# happytuesdays.net
KiCad netlist of a schematic drawn in EAGLE
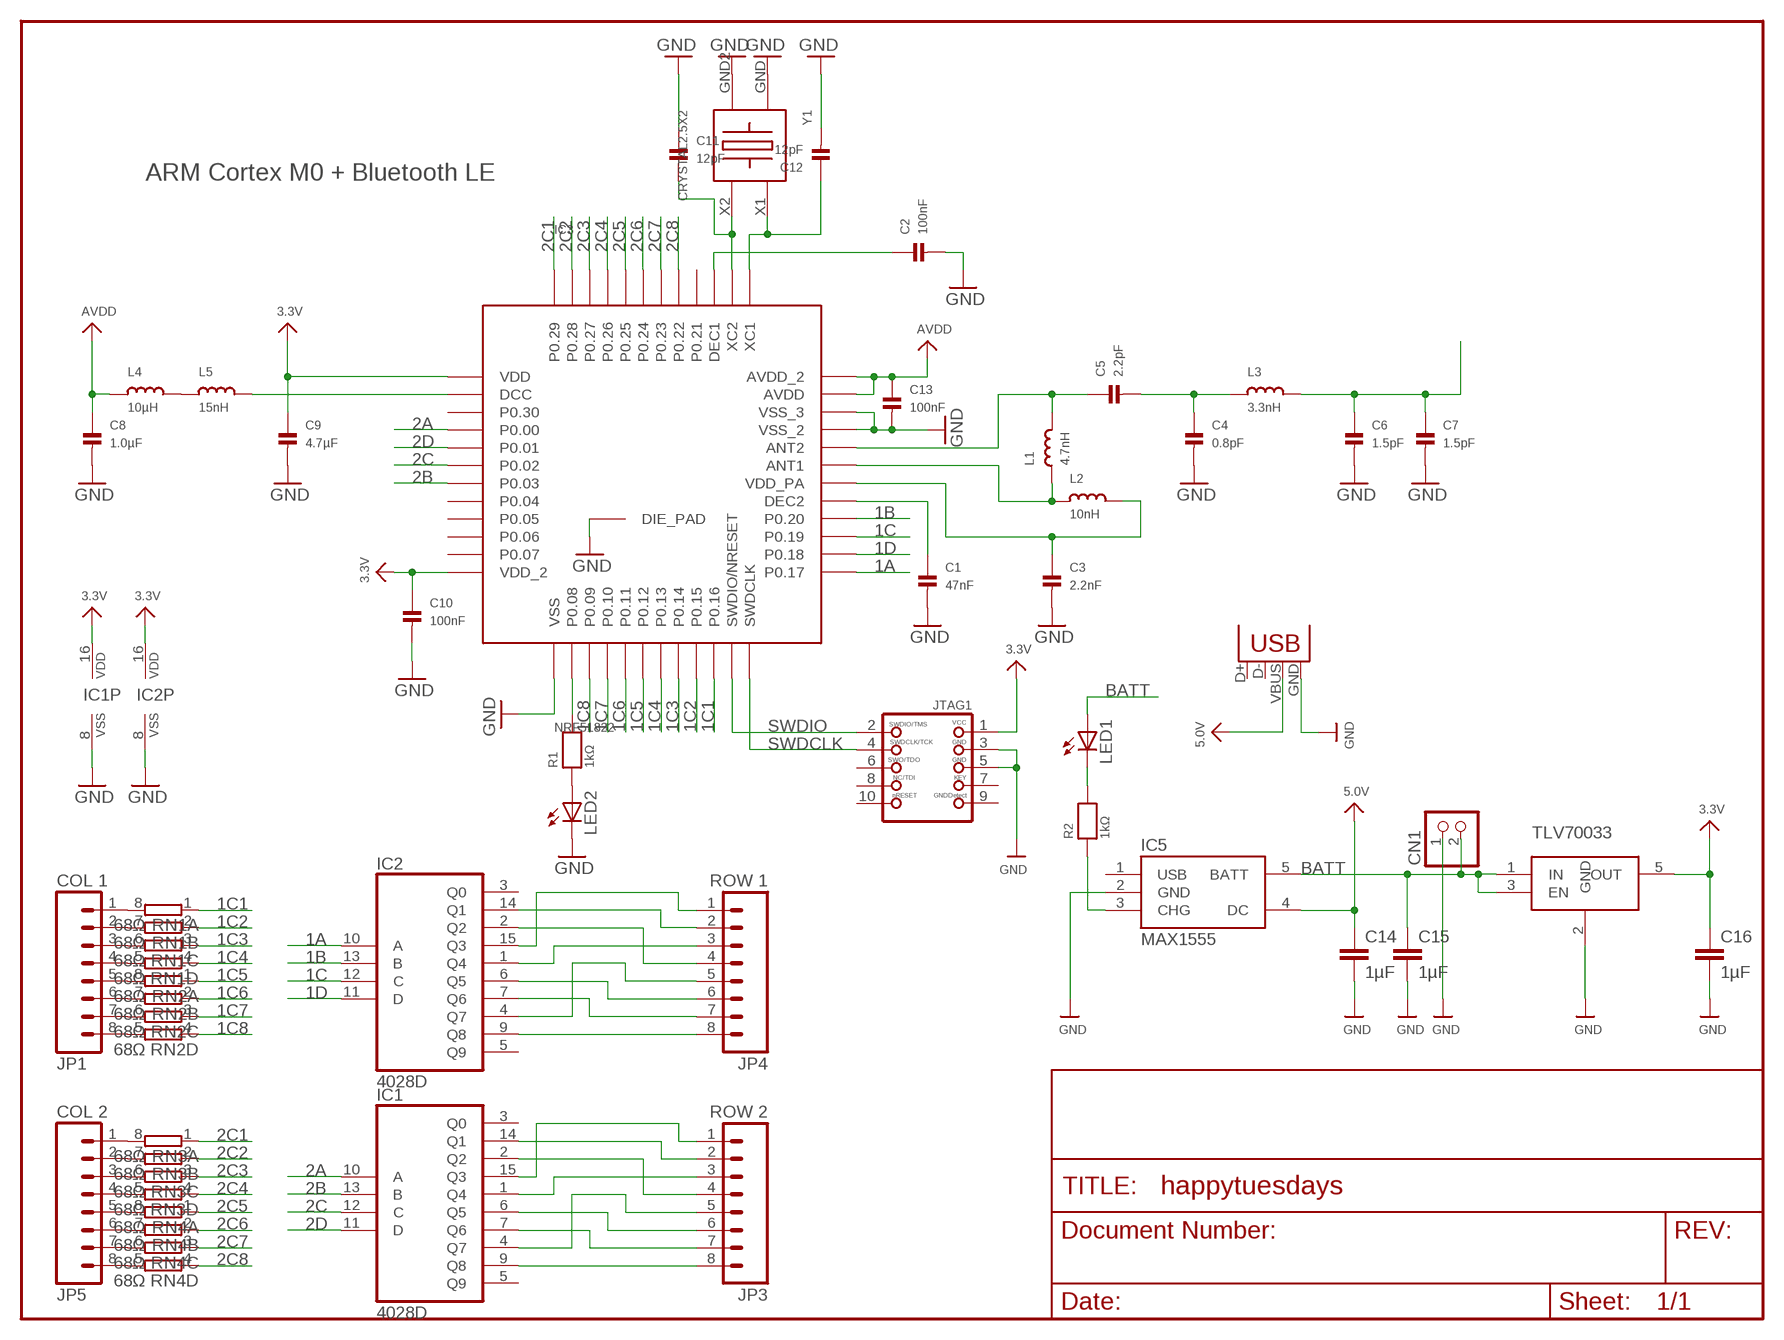
[diagram p0: schematic, sheet 1]

(export (version "E")
  (design (tool "Eeschema 10.0.6"))
  (components
    (comp (ref "C1")
      (value "47nF")
      (footprint "eagle-import:_0402")
      (libsource (lib "eagle-import") (part "CAP_CERAMIC_0402"))
    )
    (comp (ref "C2")
      (value "100nF")
      (footprint "eagle-import:_0402")
      (libsource (lib "eagle-import") (part "CAP_CERAMIC_0402"))
    )
    (comp (ref "C3")
      (value "2.2nF")
      (footprint "eagle-import:_0402")
      (libsource (lib "eagle-import") (part "CAP_CERAMIC_0402"))
    )
    (comp (ref "C4")
      (value "0.8pF")
      (footprint "eagle-import:_0402")
      (libsource (lib "eagle-import") (part "CAP_CERAMIC_0402"))
    )
    (comp (ref "C5")
      (value "2.2pF")
      (footprint "eagle-import:_0402")
      (libsource (lib "eagle-import") (part "CAP_CERAMIC_0402"))
    )
    (comp (ref "C6")
      (value "1.5pF")
      (footprint "eagle-import:_0402")
      (libsource (lib "eagle-import") (part "CAP_CERAMIC_0402"))
    )
    (comp (ref "C7")
      (value "1.5pF")
      (footprint "eagle-import:_0402")
      (libsource (lib "eagle-import") (part "CAP_CERAMIC_0402"))
    )
    (comp (ref "C8")
      (value "1.0µF")
      (footprint "eagle-import:_0402")
      (libsource (lib "eagle-import") (part "CAP_CERAMIC_0402"))
    )
    (comp (ref "C9")
      (value "4.7µF")
      (footprint "eagle-import:_0402")
      (libsource (lib "eagle-import") (part "CAP_CERAMIC_0402"))
    )
    (comp (ref "C10")
      (value "100nF")
      (footprint "eagle-import:_0402")
      (libsource (lib "eagle-import") (part "CAP_CERAMIC_0402"))
    )
    (comp (ref "C11")
      (value "12pF")
      (footprint "eagle-import:_0402")
      (libsource (lib "eagle-import") (part "CAP_CERAMIC_0402"))
    )
    (comp (ref "C12")
      (value "12pF")
      (footprint "eagle-import:_0402")
      (libsource (lib "eagle-import") (part "CAP_CERAMIC_0402"))
    )
    (comp (ref "C13")
      (value "100nF")
      (footprint "eagle-import:_0402")
      (libsource (lib "eagle-import") (part "CAP_CERAMIC_0402"))
    )
    (comp (ref "C14")
      (value "1µF")
      (footprint "eagle-import:C0603K")
      (libsource (lib "eagle-import") (part "C-EUC0603K"))
    )
    (comp (ref "C15")
      (value "1µF")
      (footprint "eagle-import:C0603K")
      (libsource (lib "eagle-import") (part "C-EUC0603K"))
    )
    (comp (ref "C16")
      (value "1µF")
      (footprint "eagle-import:C0603K")
      (libsource (lib "eagle-import") (part "C-EUC0603K"))
    )
    (comp (ref "CN1")
      (value "JST_2PIN")
      (footprint "eagle-import:JSTPH2")
      (libsource (lib "eagle-import") (part "JST_2PIN"))
    )
    (comp (ref "IC1")
      (value "4028D")
      (footprint "eagle-import:SO16")
      (libsource (lib "eagle-import") (part "4028D"))
    )
    (comp (ref "IC2")
      (value "4028D")
      (footprint "eagle-import:SO16")
      (libsource (lib "eagle-import") (part "4028D"))
    )
    (comp (ref "IC3")
      (value "NRF51822")
      (footprint "eagle-import:QFN48")
      (libsource (lib "eagle-import") (part "NRF51822"))
    )
    (comp (ref "IC4")
      (value "TLV70033DCK")
      (footprint "eagle-import:SC70-5L")
      (libsource (lib "eagle-import") (part "TLV700DCK"))
    )
    (comp (ref "IC5")
      (value "MAX1555")
      (footprint "eagle-import:SOT23-5")
      (libsource (lib "eagle-import") (part "MAX1555"))
    )
    (comp (ref "JP1")
      (value "COL 1")
      (footprint "eagle-import:1X08_LOCK")
      (libsource (lib "eagle-import") (part "M08LOCK"))
    )
    (comp (ref "JP3")
      (value "ROW 2")
      (footprint "eagle-import:1X08_LOCK")
      (libsource (lib "eagle-import") (part "M08LOCK"))
    )
    (comp (ref "JP4")
      (value "ROW 1")
      (footprint "eagle-import:1X08_LOCK")
      (libsource (lib "eagle-import") (part "M08LOCK"))
    )
    (comp (ref "JP5")
      (value "COL 2")
      (footprint "eagle-import:1X08_LOCK")
      (libsource (lib "eagle-import") (part "M08LOCK"))
    )
    (comp (ref "JTAG1")
      (value "JTAG-CORTEXM3SMT")
      (footprint "eagle-import:2X05_1.27MM_SMT")
      (libsource (lib "eagle-import") (part "JTAG-CORTEXM3SMT"))
    )
    (comp (ref "L1")
      (value "4.7nH")
      (footprint "eagle-import:_0402")
      (libsource (lib "eagle-import") (part "INDUCTOR_0402"))
    )
    (comp (ref "L2")
      (value "10nH")
      (footprint "eagle-import:_0402")
      (libsource (lib "eagle-import") (part "INDUCTOR_0402"))
    )
    (comp (ref "L3")
      (value "3.3nH")
      (footprint "eagle-import:_0402")
      (libsource (lib "eagle-import") (part "INDUCTOR_0402"))
    )
    (comp (ref "L4")
      (value "10µH")
      (footprint "eagle-import:_0402")
      (libsource (lib "eagle-import") (part "INDUCTOR_0402"))
    )
    (comp (ref "L5")
      (value "15nH")
      (footprint "eagle-import:_0402")
      (libsource (lib "eagle-import") (part "INDUCTOR_0402"))
    )
    (comp (ref "LED1")
      (value "LEDCHIPLED_0603")
      (footprint "eagle-import:CHIPLED_0603")
      (libsource (lib "eagle-import") (part "LEDCHIPLED_0603"))
    )
    (comp (ref "LED2")
      (value "LEDCHIPLED_0603")
      (footprint "eagle-import:CHIPLED_0603")
      (libsource (lib "eagle-import") (part "LEDCHIPLED_0603"))
    )
    (comp (ref "R1")
      (value "1kΩ")
      (footprint "eagle-import:_0402")
      (libsource (lib "eagle-import") (part "RESISTOR_0402"))
    )
    (comp (ref "R2")
      (value "1kΩ")
      (footprint "eagle-import:_0402")
      (libsource (lib "eagle-import") (part "RESISTOR_0402"))
    )
    (comp (ref "RN1")
      (value "68Ω")
      (footprint "eagle-import:4X0402ARV341")
      (libsource (lib "eagle-import") (part "4R-N0402ARV341"))
    )
    (comp (ref "RN2")
      (value "68Ω")
      (footprint "eagle-import:4X0402ARV341")
      (libsource (lib "eagle-import") (part "4R-N0402ARV341"))
    )
    (comp (ref "RN3")
      (value "68Ω")
      (footprint "eagle-import:4X0402ARV341")
      (libsource (lib "eagle-import") (part "4R-N0402ARV341"))
    )
    (comp (ref "RN4")
      (value "68Ω")
      (footprint "eagle-import:4X0402ARV341")
      (libsource (lib "eagle-import") (part "4R-N0402ARV341"))
    )
    (comp (ref "X1")
      (value "USB-MICROB")
      (footprint "eagle-import:USB-MICROB")
      (libsource (lib "eagle-import") (part "USB-MICROB"))
    )
    (comp (ref "Y1")
      (value "CRYSTAL2.5X2")
      (footprint "eagle-import:2.5X2MM")
      (libsource (lib "eagle-import") (part "CRYSTAL2.5X2"))
    )
  )
  (nets
    (net (code "1") (name "/1A") (class "Default")
      (node (ref "IC2") (pin "10") (pinfunction "A_10") (pintype "input"))
      (node (ref "IC3") (pin "25") (pinfunction "P0.17_25") (pintype "bidirectional"))
    )
    (net (code "2") (name "/1B") (class "Default")
      (node (ref "IC2") (pin "13") (pinfunction "B_13") (pintype "input"))
      (node (ref "IC3") (pin "28") (pinfunction "P0.20_28") (pintype "bidirectional"))
    )
    (net (code "3") (name "/1C") (class "Default")
      (node (ref "IC2") (pin "12") (pinfunction "C_12") (pintype "input"))
      (node (ref "IC3") (pin "27") (pinfunction "P0.19_27") (pintype "bidirectional"))
    )
    (net (code "4") (name "/1C1") (class "Default")
      (node (ref "IC3") (pin "22") (pinfunction "P0.16_22") (pintype "bidirectional"))
      (node (ref "RN1") (pin "1") (pinfunction "1_1") (pintype "passive"))
    )
    (net (code "5") (name "/1C2") (class "Default")
      (node (ref "IC3") (pin "21") (pinfunction "P0.15_21") (pintype "bidirectional"))
      (node (ref "RN1") (pin "2") (pinfunction "1_2") (pintype "passive"))
    )
    (net (code "6") (name "/1C3") (class "Default")
      (node (ref "IC3") (pin "20") (pinfunction "P0.14_20") (pintype "bidirectional"))
      (node (ref "RN1") (pin "3") (pinfunction "1_3") (pintype "passive"))
    )
    (net (code "7") (name "/1C4") (class "Default")
      (node (ref "IC3") (pin "19") (pinfunction "P0.13_19") (pintype "bidirectional"))
      (node (ref "RN1") (pin "4") (pinfunction "1_4") (pintype "passive"))
    )
    (net (code "8") (name "/1C5") (class "Default")
      (node (ref "IC3") (pin "18") (pinfunction "P0.12_18") (pintype "bidirectional"))
      (node (ref "RN2") (pin "1") (pinfunction "1_1") (pintype "passive"))
    )
    (net (code "9") (name "/1C6") (class "Default")
      (node (ref "IC3") (pin "17") (pinfunction "P0.11_17") (pintype "bidirectional"))
      (node (ref "RN2") (pin "2") (pinfunction "1_2") (pintype "passive"))
    )
    (net (code "10") (name "/1C7") (class "Default")
      (node (ref "IC3") (pin "16") (pinfunction "P0.10_16") (pintype "bidirectional"))
      (node (ref "RN2") (pin "3") (pinfunction "1_3") (pintype "passive"))
    )
    (net (code "11") (name "/1C8") (class "Default")
      (node (ref "IC3") (pin "15") (pinfunction "P0.09_15") (pintype "bidirectional"))
      (node (ref "RN2") (pin "4") (pinfunction "1_4") (pintype "passive"))
    )
    (net (code "12") (name "/1D") (class "Default")
      (node (ref "IC2") (pin "11") (pinfunction "D_11") (pintype "input"))
      (node (ref "IC3") (pin "26") (pinfunction "P0.18_26") (pintype "bidirectional"))
    )
    (net (code "13") (name "/2A") (class "Default")
      (node (ref "IC1") (pin "10") (pinfunction "A_10") (pintype "input"))
      (node (ref "IC3") (pin "4") (pinfunction "P0.00_4") (pintype "bidirectional"))
    )
    (net (code "14") (name "/2B") (class "Default")
      (node (ref "IC1") (pin "13") (pinfunction "B_13") (pintype "input"))
      (node (ref "IC3") (pin "7") (pinfunction "P0.03_7") (pintype "bidirectional"))
    )
    (net (code "15") (name "/2C") (class "Default")
      (node (ref "IC1") (pin "12") (pinfunction "C_12") (pintype "input"))
      (node (ref "IC3") (pin "6") (pinfunction "P0.02_6") (pintype "bidirectional"))
    )
    (net (code "16") (name "/2C1") (class "Default")
      (node (ref "IC3") (pin "48") (pinfunction "P0.29_48") (pintype "bidirectional"))
      (node (ref "RN3") (pin "1") (pinfunction "1_1") (pintype "passive"))
    )
    (net (code "17") (name "/2C2") (class "Default")
      (node (ref "IC3") (pin "47") (pinfunction "P0.28_47") (pintype "bidirectional"))
      (node (ref "RN3") (pin "2") (pinfunction "1_2") (pintype "passive"))
    )
    (net (code "18") (name "/2C3") (class "Default")
      (node (ref "IC3") (pin "46") (pinfunction "P0.27_46") (pintype "bidirectional"))
      (node (ref "RN3") (pin "3") (pinfunction "1_3") (pintype "passive"))
    )
    (net (code "19") (name "/2C4") (class "Default")
      (node (ref "IC3") (pin "45") (pinfunction "P0.26_45") (pintype "bidirectional"))
      (node (ref "RN3") (pin "4") (pinfunction "1_4") (pintype "passive"))
    )
    (net (code "20") (name "/2C5") (class "Default")
      (node (ref "IC3") (pin "44") (pinfunction "P0.25_44") (pintype "bidirectional"))
      (node (ref "RN4") (pin "1") (pinfunction "1_1") (pintype "passive"))
    )
    (net (code "21") (name "/2C6") (class "Default")
      (node (ref "IC3") (pin "43") (pinfunction "P0.24_43") (pintype "bidirectional"))
      (node (ref "RN4") (pin "2") (pinfunction "1_2") (pintype "passive"))
    )
    (net (code "22") (name "/2C7") (class "Default")
      (node (ref "IC3") (pin "42") (pinfunction "P0.23_42") (pintype "bidirectional"))
      (node (ref "RN4") (pin "3") (pinfunction "1_3") (pintype "passive"))
    )
    (net (code "23") (name "/2C8") (class "Default")
      (node (ref "IC3") (pin "41") (pinfunction "P0.22_41") (pintype "bidirectional"))
      (node (ref "RN4") (pin "4") (pinfunction "1_4") (pintype "passive"))
    )
    (net (code "24") (name "/2D") (class "Default")
      (node (ref "IC1") (pin "11") (pinfunction "D_11") (pintype "input"))
      (node (ref "IC3") (pin "5") (pinfunction "P0.01_5") (pintype "bidirectional"))
    )
    (net (code "25") (name "/BATT") (class "Default")
      (node (ref "C15") (pin "1") (pinfunction "1_1") (pintype "passive"))
      (node (ref "CN1") (pin "2") (pinfunction "2_2") (pintype "passive"))
      (node (ref "IC4") (pin "1") (pinfunction "IN_1") (pintype "bidirectional"))
      (node (ref "IC4") (pin "3") (pinfunction "EN_3") (pintype "bidirectional"))
      (node (ref "IC5") (pin "5") (pinfunction "BATT_5") (pintype "bidirectional"))
      (node (ref "LED1") (pin "A") (pinfunction "A_A") (pintype "passive"))
    )
    (net (code "26") (name "/SWDCLK") (class "Default")
      (node (ref "IC3") (pin "24") (pinfunction "SWDCLK_24") (pintype "bidirectional"))
      (node (ref "JTAG1") (pin "4") (pinfunction "4_4") (pintype "passive"))
    )
    (net (code "27") (name "/SWDIO") (class "Default")
      (node (ref "IC3") (pin "23") (pinfunction "SWDIO/NRESET_23") (pintype "bidirectional"))
      (node (ref "JTAG1") (pin "2") (pinfunction "2_2") (pintype "passive"))
    )
    (net (code "28") (name "3.3V") (class "Default")
      (node (ref "C10") (pin "1") (pinfunction "P$1_1") (pintype "passive"))
      (node (ref "C16") (pin "1") (pinfunction "1_1") (pintype "passive"))
      (node (ref "C9") (pin "1") (pinfunction "P$1_1") (pintype "passive"))
      (node (ref "IC1") (pin "16") (pinfunction "VDD_16") (pintype "power_in"))
      (node (ref "IC2") (pin "16") (pinfunction "VDD_16") (pintype "power_in"))
      (node (ref "IC3") (pin "1") (pinfunction "VDD_1") (pintype "bidirectional"))
      (node (ref "IC3") (pin "12") (pinfunction "VDD_2_12") (pintype "bidirectional"))
      (node (ref "IC4") (pin "5") (pinfunction "OUT_5") (pintype "bidirectional"))
      (node (ref "JTAG1") (pin "1") (pinfunction "1_1") (pintype "passive"))
    )
    (net (code "29") (name "5.0V") (class "Default")
      (node (ref "C14") (pin "1") (pinfunction "1_1") (pintype "passive"))
      (node (ref "IC5") (pin "4") (pinfunction "DC_4") (pintype "bidirectional"))
      (node (ref "X1") (pin "VBUS") (pinfunction "VBUS_VBUS") (pintype "bidirectional"))
    )
    (net (code "30") (name "AVDD") (class "Default")
      (node (ref "C13") (pin "1") (pinfunction "P$1_1") (pintype "passive"))
      (node (ref "C8") (pin "1") (pinfunction "P$1_1") (pintype "passive"))
      (node (ref "IC3") (pin "35") (pinfunction "AVDD_35") (pintype "bidirectional"))
      (node (ref "IC3") (pin "36") (pinfunction "AVDD_2_36") (pintype "bidirectional"))
      (node (ref "L4") (pin "1") (pinfunction "1_1") (pintype "passive"))
    )
    (net (code "31") (name "GND") (class "Default")
      (node (ref "C1") (pin "2") (pinfunction "P$2_2") (pintype "passive"))
      (node (ref "C10") (pin "2") (pinfunction "P$2_2") (pintype "passive"))
      (node (ref "C11") (pin "1") (pinfunction "P$1_1") (pintype "passive"))
      (node (ref "C12") (pin "2") (pinfunction "P$2_2") (pintype "passive"))
      (node (ref "C13") (pin "2") (pinfunction "P$2_2") (pintype "passive"))
      (node (ref "C14") (pin "2") (pinfunction "2_2") (pintype "passive"))
      (node (ref "C15") (pin "2") (pinfunction "2_2") (pintype "passive"))
      (node (ref "C16") (pin "2") (pinfunction "2_2") (pintype "passive"))
      (node (ref "C2") (pin "2") (pinfunction "P$2_2") (pintype "passive"))
      (node (ref "C3") (pin "2") (pinfunction "P$2_2") (pintype "passive"))
      (node (ref "C4") (pin "2") (pinfunction "P$2_2") (pintype "passive"))
      (node (ref "C6") (pin "2") (pinfunction "P$2_2") (pintype "passive"))
      (node (ref "C7") (pin "2") (pinfunction "P$2_2") (pintype "passive"))
      (node (ref "C8") (pin "2") (pinfunction "P$2_2") (pintype "passive"))
      (node (ref "C9") (pin "2") (pinfunction "P$2_2") (pintype "passive"))
      (node (ref "CN1") (pin "1") (pinfunction "1_1") (pintype "passive"))
      (node (ref "IC1") (pin "8") (pinfunction "VSS_8") (pintype "power_in"))
      (node (ref "IC2") (pin "8") (pinfunction "VSS_8") (pintype "power_in"))
      (node (ref "IC3") (pin "13") (pinfunction "VSS_13") (pintype "bidirectional"))
      (node (ref "IC3") (pin "33") (pinfunction "VSS_2_33") (pintype "bidirectional"))
      (node (ref "IC3") (pin "34") (pinfunction "VSS_3_34") (pintype "bidirectional"))
      (node (ref "IC3") (pin "GND") (pinfunction "DIE_PAD_GND") (pintype "bidirectional"))
      (node (ref "IC4") (pin "2") (pinfunction "GND_2") (pintype "bidirectional"))
      (node (ref "IC5") (pin "2") (pinfunction "GND_2") (pintype "bidirectional"))
      (node (ref "JTAG1") (pin "3") (pinfunction "3_3") (pintype "passive"))
      (node (ref "JTAG1") (pin "5") (pinfunction "5_5") (pintype "passive"))
      (node (ref "LED2") (pin "C") (pinfunction "C_C") (pintype "passive"))
      (node (ref "X1") (pin "GND") (pinfunction "GND_GND") (pintype "bidirectional"))
      (node (ref "Y1") (pin "GND") (pinfunction "GND_GND") (pintype "bidirectional"))
      (node (ref "Y1") (pin "GND2") (pinfunction "GND2_GND2") (pintype "bidirectional"))
    )
    (net (code "32") (name "Net-(C1-P$1)") (class "Default")
      (node (ref "C1") (pin "1") (pinfunction "P$1_1") (pintype "passive"))
      (node (ref "IC3") (pin "29") (pinfunction "DEC2_29") (pintype "bidirectional"))
    )
    (net (code "33") (name "Net-(C2-P$1)") (class "Default")
      (node (ref "C2") (pin "1") (pinfunction "P$1_1") (pintype "passive"))
      (node (ref "IC3") (pin "39") (pinfunction "DEC1_39") (pintype "bidirectional"))
    )
    (net (code "34") (name "Net-(C3-P$1)") (class "Default")
      (node (ref "C3") (pin "1") (pinfunction "P$1_1") (pintype "passive"))
      (node (ref "IC3") (pin "30") (pinfunction "VDD_PA_30") (pintype "bidirectional"))
      (node (ref "L2") (pin "2") (pinfunction "2_2") (pintype "passive"))
    )
    (net (code "35") (name "Net-(C4-P$1)") (class "Default")
      (node (ref "C4") (pin "1") (pinfunction "P$1_1") (pintype "passive"))
      (node (ref "C5") (pin "2") (pinfunction "P$2_2") (pintype "passive"))
      (node (ref "L3") (pin "1") (pinfunction "1_1") (pintype "passive"))
    )
    (net (code "36") (name "Net-(C5-P$1)") (class "Default")
      (node (ref "C5") (pin "1") (pinfunction "P$1_1") (pintype "passive"))
      (node (ref "IC3") (pin "32") (pinfunction "ANT2_32") (pintype "bidirectional"))
      (node (ref "L1") (pin "2") (pinfunction "2_2") (pintype "passive"))
    )
    (net (code "37") (name "Net-(C6-P$1)") (class "Default")
      (node (ref "C6") (pin "1") (pinfunction "P$1_1") (pintype "passive"))
      (node (ref "C7") (pin "1") (pinfunction "P$1_1") (pintype "passive"))
      (node (ref "L3") (pin "2") (pinfunction "2_2") (pintype "passive"))
    )
    (net (code "38") (name "Net-(C11-P$2)") (class "Default")
      (node (ref "C11") (pin "2") (pinfunction "P$2_2") (pintype "passive"))
      (node (ref "IC3") (pin "38") (pinfunction "XC2_38") (pintype "bidirectional"))
      (node (ref "Y1") (pin "X2") (pinfunction "X2_X2") (pintype "bidirectional"))
    )
    (net (code "39") (name "Net-(C12-P$1)") (class "Default")
      (node (ref "C12") (pin "1") (pinfunction "P$1_1") (pintype "passive"))
      (node (ref "IC3") (pin "37") (pinfunction "XC1_37") (pintype "bidirectional"))
      (node (ref "Y1") (pin "X1") (pinfunction "X1_X1") (pintype "bidirectional"))
    )
    (net (code "40") (name "Net-(IC1A-Q1)") (class "Default")
      (node (ref "IC1") (pin "14") (pinfunction "Q1_14") (pintype "output"))
      (node (ref "JP3") (pin "2") (pinfunction "2_2") (pintype "passive"))
    )
    (net (code "41") (name "Net-(IC1A-Q2)") (class "Default")
      (node (ref "IC1") (pin "2") (pinfunction "Q2_2") (pintype "output"))
      (node (ref "JP3") (pin "4") (pinfunction "4_4") (pintype "passive"))
    )
    (net (code "42") (name "Net-(IC1A-Q3)") (class "Default")
      (node (ref "IC1") (pin "15") (pinfunction "Q3_15") (pintype "output"))
      (node (ref "JP3") (pin "1") (pinfunction "1_1") (pintype "passive"))
    )
    (net (code "43") (name "Net-(IC1A-Q4)") (class "Default")
      (node (ref "IC1") (pin "1") (pinfunction "Q4_1") (pintype "output"))
      (node (ref "JP3") (pin "3") (pinfunction "3_3") (pintype "passive"))
    )
    (net (code "44") (name "Net-(IC1A-Q5)") (class "Default")
      (node (ref "IC1") (pin "6") (pinfunction "Q5_6") (pintype "output"))
      (node (ref "JP3") (pin "6") (pinfunction "6_6") (pintype "passive"))
    )
    (net (code "45") (name "Net-(IC1A-Q6)") (class "Default")
      (node (ref "IC1") (pin "7") (pinfunction "Q6_7") (pintype "output"))
      (node (ref "JP3") (pin "7") (pinfunction "7_7") (pintype "passive"))
    )
    (net (code "46") (name "Net-(IC1A-Q7)") (class "Default")
      (node (ref "IC1") (pin "4") (pinfunction "Q7_4") (pintype "output"))
      (node (ref "JP3") (pin "5") (pinfunction "5_5") (pintype "passive"))
    )
    (net (code "47") (name "Net-(IC1A-Q8)") (class "Default")
      (node (ref "IC1") (pin "9") (pinfunction "Q8_9") (pintype "output"))
      (node (ref "JP3") (pin "8") (pinfunction "8_8") (pintype "passive"))
    )
    (net (code "48") (name "Net-(IC2A-Q1)") (class "Default")
      (node (ref "IC2") (pin "14") (pinfunction "Q1_14") (pintype "output"))
      (node (ref "JP4") (pin "2") (pinfunction "2_2") (pintype "passive"))
    )
    (net (code "49") (name "Net-(IC2A-Q2)") (class "Default")
      (node (ref "IC2") (pin "2") (pinfunction "Q2_2") (pintype "output"))
      (node (ref "JP4") (pin "4") (pinfunction "4_4") (pintype "passive"))
    )
    (net (code "50") (name "Net-(IC2A-Q3)") (class "Default")
      (node (ref "IC2") (pin "15") (pinfunction "Q3_15") (pintype "output"))
      (node (ref "JP4") (pin "1") (pinfunction "1_1") (pintype "passive"))
    )
    (net (code "51") (name "Net-(IC2A-Q4)") (class "Default")
      (node (ref "IC2") (pin "1") (pinfunction "Q4_1") (pintype "output"))
      (node (ref "JP4") (pin "3") (pinfunction "3_3") (pintype "passive"))
    )
    (net (code "52") (name "Net-(IC2A-Q5)") (class "Default")
      (node (ref "IC2") (pin "6") (pinfunction "Q5_6") (pintype "output"))
      (node (ref "JP4") (pin "6") (pinfunction "6_6") (pintype "passive"))
    )
    (net (code "53") (name "Net-(IC2A-Q6)") (class "Default")
      (node (ref "IC2") (pin "7") (pinfunction "Q6_7") (pintype "output"))
      (node (ref "JP4") (pin "7") (pinfunction "7_7") (pintype "passive"))
    )
    (net (code "54") (name "Net-(IC2A-Q7)") (class "Default")
      (node (ref "IC2") (pin "4") (pinfunction "Q7_4") (pintype "output"))
      (node (ref "JP4") (pin "5") (pinfunction "5_5") (pintype "passive"))
    )
    (net (code "55") (name "Net-(IC2A-Q8)") (class "Default")
      (node (ref "IC2") (pin "9") (pinfunction "Q8_9") (pintype "output"))
      (node (ref "JP4") (pin "8") (pinfunction "8_8") (pintype "passive"))
    )
    (net (code "56") (name "Net-(IC3-ANT1)") (class "Default")
      (node (ref "IC3") (pin "31") (pinfunction "ANT1_31") (pintype "bidirectional"))
      (node (ref "L1") (pin "1") (pinfunction "1_1") (pintype "passive"))
      (node (ref "L2") (pin "1") (pinfunction "1_1") (pintype "passive"))
    )
    (net (code "57") (name "Net-(IC3-DCC)") (class "Default")
      (node (ref "IC3") (pin "2") (pinfunction "DCC_2") (pintype "bidirectional"))
      (node (ref "L5") (pin "2") (pinfunction "2_2") (pintype "passive"))
    )
    (net (code "58") (name "Net-(IC3-P0.08)") (class "Default")
      (node (ref "IC3") (pin "14") (pinfunction "P0.08_14") (pintype "bidirectional"))
      (node (ref "R1") (pin "2") (pinfunction "2_2") (pintype "passive"))
    )
    (net (code "59") (name "Net-(IC5-CHG)") (class "Default")
      (node (ref "IC5") (pin "3") (pinfunction "CHG_3") (pintype "bidirectional"))
      (node (ref "R2") (pin "1") (pinfunction "1_1") (pintype "passive"))
    )
    (net (code "60") (name "Net-(L4-Pad2)") (class "Default")
      (node (ref "L4") (pin "2") (pinfunction "2_2") (pintype "passive"))
      (node (ref "L5") (pin "1") (pinfunction "1_1") (pintype "passive"))
    )
    (net (code "61") (name "Net-(LED1-PadC)") (class "Default")
      (node (ref "LED1") (pin "C") (pinfunction "C_C") (pintype "passive"))
      (node (ref "R2") (pin "2") (pinfunction "2_2") (pintype "passive"))
    )
    (net (code "62") (name "Net-(LED2-PadA)") (class "Default")
      (node (ref "LED2") (pin "A") (pinfunction "A_A") (pintype "passive"))
      (node (ref "R1") (pin "1") (pinfunction "1_1") (pintype "passive"))
    )
    (net (code "63") (name "Net-(RN1A-2)") (class "Default")
      (node (ref "JP1") (pin "1") (pinfunction "1_1") (pintype "passive"))
      (node (ref "RN1") (pin "8") (pinfunction "2_8") (pintype "passive"))
    )
    (net (code "64") (name "Net-(RN1B-2)") (class "Default")
      (node (ref "JP1") (pin "2") (pinfunction "2_2") (pintype "passive"))
      (node (ref "RN1") (pin "7") (pinfunction "2_7") (pintype "passive"))
    )
    (net (code "65") (name "Net-(RN1C-2)") (class "Default")
      (node (ref "JP1") (pin "3") (pinfunction "3_3") (pintype "passive"))
      (node (ref "RN1") (pin "6") (pinfunction "2_6") (pintype "passive"))
    )
    (net (code "66") (name "Net-(RN1D-2)") (class "Default")
      (node (ref "JP1") (pin "4") (pinfunction "4_4") (pintype "passive"))
      (node (ref "RN1") (pin "5") (pinfunction "2_5") (pintype "passive"))
    )
    (net (code "67") (name "Net-(RN2A-2)") (class "Default")
      (node (ref "JP1") (pin "5") (pinfunction "5_5") (pintype "passive"))
      (node (ref "RN2") (pin "8") (pinfunction "2_8") (pintype "passive"))
    )
    (net (code "68") (name "Net-(RN2B-2)") (class "Default")
      (node (ref "JP1") (pin "6") (pinfunction "6_6") (pintype "passive"))
      (node (ref "RN2") (pin "7") (pinfunction "2_7") (pintype "passive"))
    )
    (net (code "69") (name "Net-(RN2C-2)") (class "Default")
      (node (ref "JP1") (pin "7") (pinfunction "7_7") (pintype "passive"))
      (node (ref "RN2") (pin "6") (pinfunction "2_6") (pintype "passive"))
    )
    (net (code "70") (name "Net-(RN2D-2)") (class "Default")
      (node (ref "JP1") (pin "8") (pinfunction "8_8") (pintype "passive"))
      (node (ref "RN2") (pin "5") (pinfunction "2_5") (pintype "passive"))
    )
    (net (code "71") (name "Net-(RN3A-2)") (class "Default")
      (node (ref "JP5") (pin "1") (pinfunction "1_1") (pintype "passive"))
      (node (ref "RN3") (pin "8") (pinfunction "2_8") (pintype "passive"))
    )
    (net (code "72") (name "Net-(RN3B-2)") (class "Default")
      (node (ref "JP5") (pin "2") (pinfunction "2_2") (pintype "passive"))
      (node (ref "RN3") (pin "7") (pinfunction "2_7") (pintype "passive"))
    )
    (net (code "73") (name "Net-(RN3C-2)") (class "Default")
      (node (ref "JP5") (pin "3") (pinfunction "3_3") (pintype "passive"))
      (node (ref "RN3") (pin "6") (pinfunction "2_6") (pintype "passive"))
    )
    (net (code "74") (name "Net-(RN3D-2)") (class "Default")
      (node (ref "JP5") (pin "4") (pinfunction "4_4") (pintype "passive"))
      (node (ref "RN3") (pin "5") (pinfunction "2_5") (pintype "passive"))
    )
    (net (code "75") (name "Net-(RN4A-2)") (class "Default")
      (node (ref "JP5") (pin "5") (pinfunction "5_5") (pintype "passive"))
      (node (ref "RN4") (pin "8") (pinfunction "2_8") (pintype "passive"))
    )
    (net (code "76") (name "Net-(RN4B-2)") (class "Default")
      (node (ref "JP5") (pin "6") (pinfunction "6_6") (pintype "passive"))
      (node (ref "RN4") (pin "7") (pinfunction "2_7") (pintype "passive"))
    )
    (net (code "77") (name "Net-(RN4C-2)") (class "Default")
      (node (ref "JP5") (pin "7") (pinfunction "7_7") (pintype "passive"))
      (node (ref "RN4") (pin "6") (pinfunction "2_6") (pintype "passive"))
    )
    (net (code "78") (name "Net-(RN4D-2)") (class "Default")
      (node (ref "JP5") (pin "8") (pinfunction "8_8") (pintype "passive"))
      (node (ref "RN4") (pin "5") (pinfunction "2_5") (pintype "passive"))
    )
    (net (code "79") (name "unconnected-(IC1A-Q0-Pad3)") (class "Default")
      (node (ref "IC1") (pin "3") (pinfunction "Q0_3") (pintype "output"))
    )
    (net (code "80") (name "unconnected-(IC1A-Q9-Pad5)") (class "Default")
      (node (ref "IC1") (pin "5") (pinfunction "Q9_5") (pintype "output"))
    )
    (net (code "81") (name "unconnected-(IC2A-Q0-Pad3)") (class "Default")
      (node (ref "IC2") (pin "3") (pinfunction "Q0_3") (pintype "output"))
    )
    (net (code "82") (name "unconnected-(IC2A-Q9-Pad5)") (class "Default")
      (node (ref "IC2") (pin "5") (pinfunction "Q9_5") (pintype "output"))
    )
    (net (code "83") (name "unconnected-(IC3-P0.04-Pad8)") (class "Default")
      (node (ref "IC3") (pin "8") (pinfunction "P0.04_8") (pintype "bidirectional"))
    )
    (net (code "84") (name "unconnected-(IC3-P0.05-Pad9)") (class "Default")
      (node (ref "IC3") (pin "9") (pinfunction "P0.05_9") (pintype "bidirectional"))
    )
    (net (code "85") (name "unconnected-(IC3-P0.06-Pad10)") (class "Default")
      (node (ref "IC3") (pin "10") (pinfunction "P0.06_10") (pintype "bidirectional"))
    )
    (net (code "86") (name "unconnected-(IC3-P0.07-Pad11)") (class "Default")
      (node (ref "IC3") (pin "11") (pinfunction "P0.07_11") (pintype "bidirectional"))
    )
    (net (code "87") (name "unconnected-(IC3-P0.21-Pad40)") (class "Default")
      (node (ref "IC3") (pin "40") (pinfunction "P0.21_40") (pintype "bidirectional"))
    )
    (net (code "88") (name "unconnected-(IC3-P0.30-Pad3)") (class "Default")
      (node (ref "IC3") (pin "3") (pinfunction "P0.30_3") (pintype "bidirectional"))
    )
    (net (code "89") (name "unconnected-(IC5-USB-Pad1)") (class "Default")
      (node (ref "IC5") (pin "1") (pinfunction "USB_1") (pintype "bidirectional"))
    )
    (net (code "90") (name "unconnected-(JTAG1-Pad6)") (class "Default")
      (node (ref "JTAG1") (pin "6") (pinfunction "6_6") (pintype "passive"))
    )
    (net (code "91") (name "unconnected-(JTAG1-Pad7)") (class "Default")
      (node (ref "JTAG1") (pin "7") (pinfunction "7_7") (pintype "passive"))
    )
    (net (code "92") (name "unconnected-(JTAG1-Pad8)") (class "Default")
      (node (ref "JTAG1") (pin "8") (pinfunction "8_8") (pintype "passive"))
    )
    (net (code "93") (name "unconnected-(JTAG1-Pad9)") (class "Default")
      (node (ref "JTAG1") (pin "9") (pinfunction "9_9") (pintype "passive"))
    )
    (net (code "94") (name "unconnected-(JTAG1-Pad10)") (class "Default")
      (node (ref "JTAG1") (pin "10") (pinfunction "10_10") (pintype "passive"))
    )
    (net (code "95") (name "unconnected-(X1-PadD+)") (class "Default")
      (node (ref "X1") (pin "D+") (pinfunction "D+_D+") (pintype "bidirectional"))
    )
    (net (code "96") (name "unconnected-(X1-PadD-)") (class "Default")
      (node (ref "X1") (pin "D-") (pinfunction "D-_D-") (pintype "bidirectional"))
    )
  )
)
